# magnet_v2.net
KiCad netlist of a schematic drawn in EAGLE
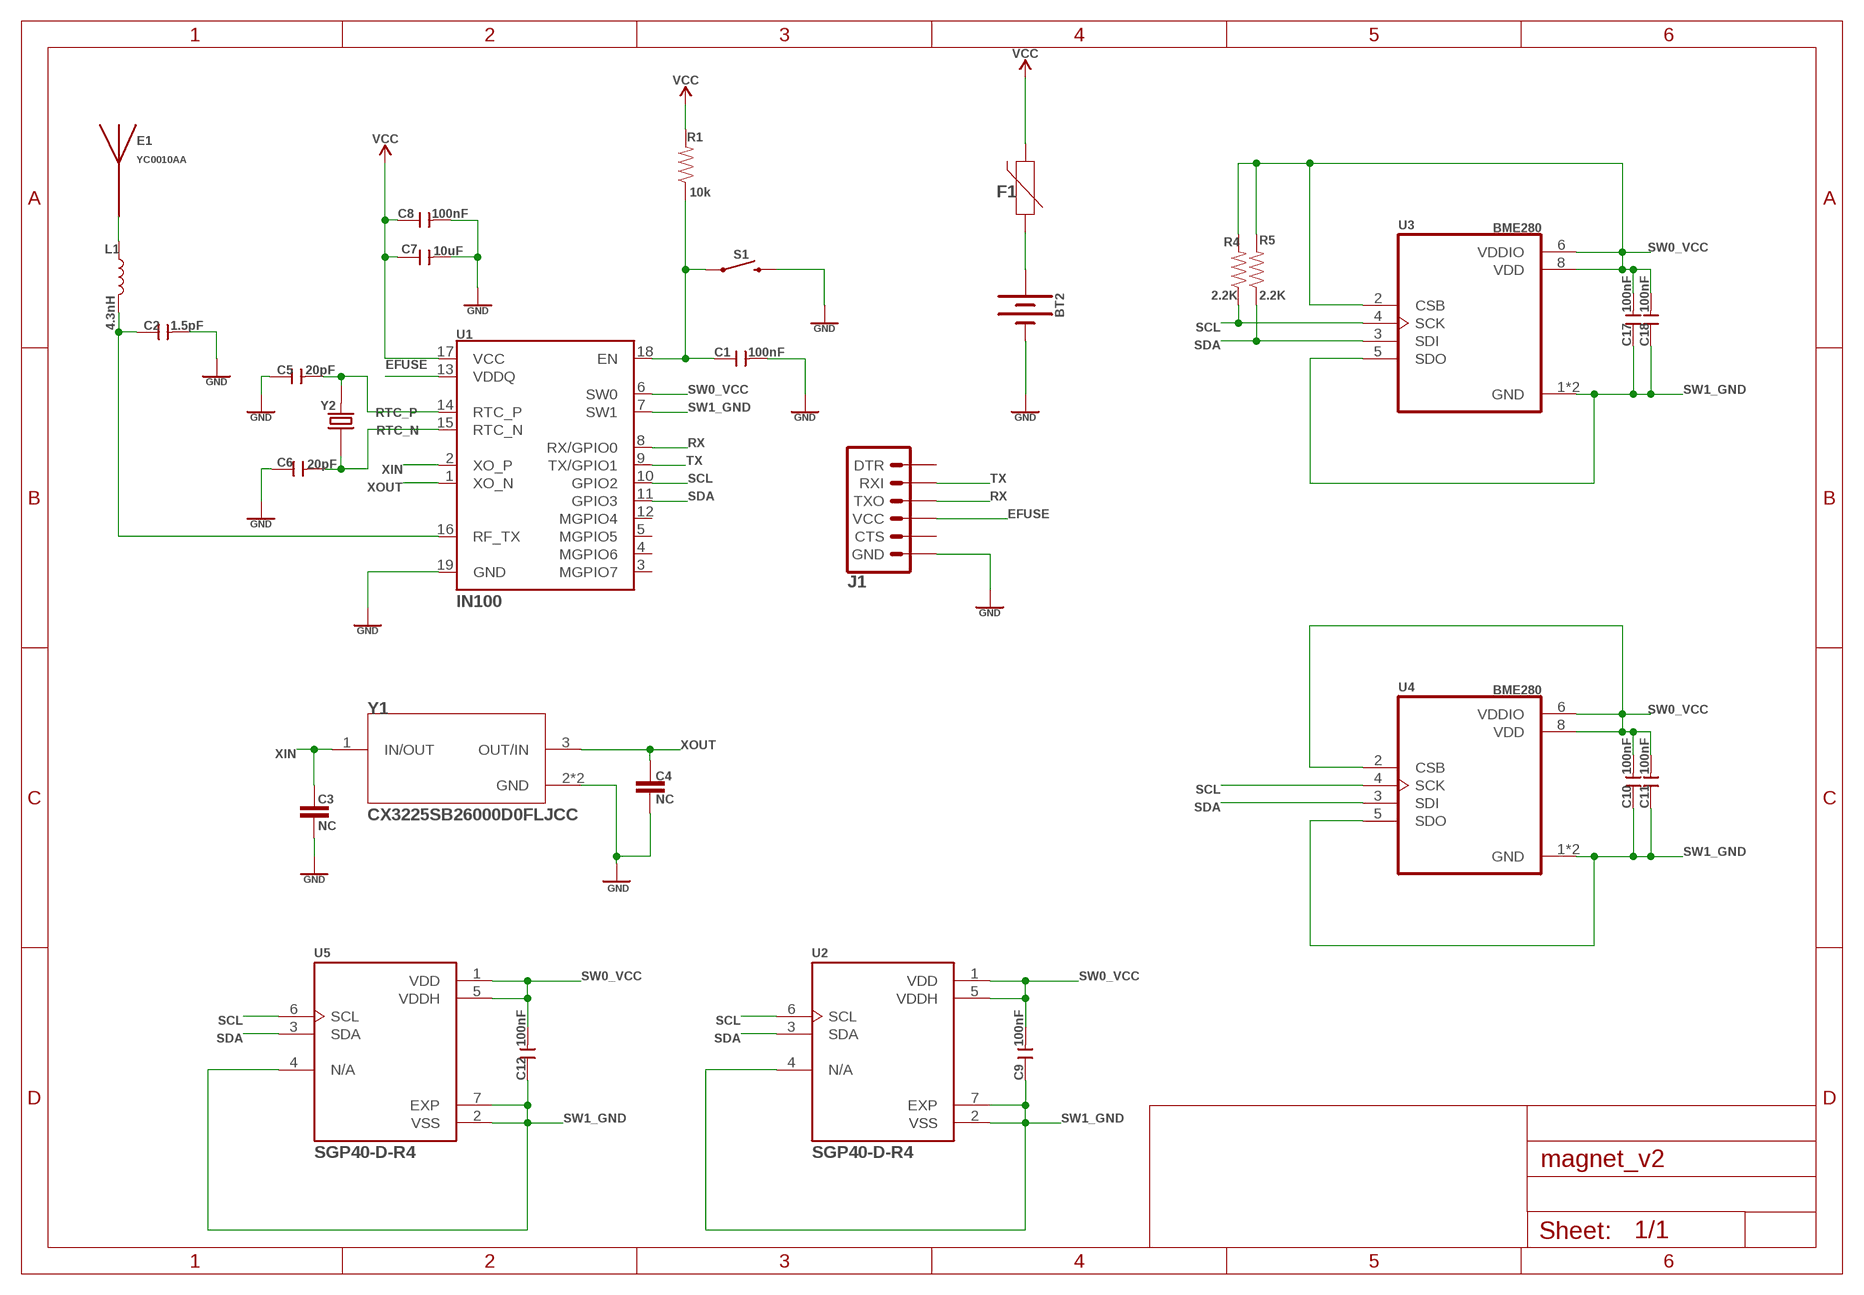
[diagram p0: schematic, sheet 1]

(export (version "E")
  (design (tool "Eeschema 10.0.6"))
  (components
    (comp (ref "BT2")
      (value "BATTERY-12MM_SMD")
      (footprint "eagle-import:BATTCON_12MM")
      (libsource (lib "eagle-import") (part "BATTERY-12MM_SMD"))
    )
    (comp (ref "C1")
      (value "100nF")
      (footprint "eagle-import:C0603")
      (fields (field (name "MPN") "CC0603KRX7R9BB104"))
      (libsource (lib "eagle-import") (part "CERAMIC-100NF-50V-10%-X7R(0603)"))
    )
    (comp (ref "C2")
      (value "1.5pF")
      (footprint "eagle-import:C0603")
      (fields (field (name "MPN") "CC0603JRNPO9BN100"))
      (libsource (lib "eagle-import") (part "CERAMIC-10PF-50V-5%-NPO(0603)"))
    )
    (comp (ref "C3")
      (value "NC")
      (footprint "eagle-import:0603")
      (libsource (lib "eagle-import") (part "12PF-0603-50V-5%"))
    )
    (comp (ref "C4")
      (value "NC")
      (footprint "eagle-import:0603")
      (libsource (lib "eagle-import") (part "12PF-0603-50V-5%"))
    )
    (comp (ref "C5")
      (value "20pF")
      (footprint "eagle-import:C0603")
      (fields (field (name "MPN") "CC0603JRNPO9BN220"))
      (libsource (lib "eagle-import") (part "CERAMIC-22PF-50V-5%-NPO(0603)"))
    )
    (comp (ref "C6")
      (value "20pF")
      (footprint "eagle-import:C0603")
      (fields (field (name "MPN") "CC0603JRNPO9BN220"))
      (libsource (lib "eagle-import") (part "CERAMIC-22PF-50V-5%-NPO(0603)"))
    )
    (comp (ref "C7")
      (value "10uF")
      (footprint "eagle-import:C0603")
      (fields (field (name "MPN") "CC0603KRX5R6BB106"))
      (libsource (lib "eagle-import") (part "CERAMIC-10UF-10V-10%-X5R(0603)"))
    )
    (comp (ref "C8")
      (value "100nF")
      (footprint "eagle-import:C0603")
      (fields (field (name "MPN") "CC0603KRX7R9BB104"))
      (libsource (lib "eagle-import") (part "CERAMIC-100NF-50V-10%-X7R(0603)"))
    )
    (comp (ref "C9")
      (value "100nF")
      (footprint "eagle-import:C0603")
      (fields (field (name "MPN") "CC0603KRX7R9BB104"))
      (libsource (lib "eagle-import") (part "CERAMIC-100NF-50V-10%-X7R(0603)"))
    )
    (comp (ref "C10")
      (value "100nF")
      (footprint "eagle-import:C0603")
      (fields (field (name "MPN") "CC0603KRX7R9BB104"))
      (libsource (lib "eagle-import") (part "CERAMIC-100NF-50V-10%-X7R(0603)"))
    )
    (comp (ref "C11")
      (value "100nF")
      (footprint "eagle-import:C0603")
      (fields (field (name "MPN") "CC0603KRX7R9BB104"))
      (libsource (lib "eagle-import") (part "CERAMIC-100NF-50V-10%-X7R(0603)"))
    )
    (comp (ref "C12")
      (value "100nF")
      (footprint "eagle-import:C0603")
      (fields (field (name "MPN") "CC0603KRX7R9BB104"))
      (libsource (lib "eagle-import") (part "CERAMIC-100NF-50V-10%-X7R(0603)"))
    )
    (comp (ref "C17")
      (value "100nF")
      (footprint "eagle-import:C0603")
      (fields (field (name "MPN") "CC0603KRX7R9BB104"))
      (libsource (lib "eagle-import") (part "CERAMIC-100NF-50V-10%-X7R(0603)"))
    )
    (comp (ref "C18")
      (value "100nF")
      (footprint "eagle-import:C0603")
      (fields (field (name "MPN") "CC0603KRX7R9BB104"))
      (libsource (lib "eagle-import") (part "CERAMIC-100NF-50V-10%-X7R(0603)"))
    )
    (comp (ref "E1")
      (value "YC0010AA")
      (footprint "eagle-import:XCVR_YC0010AA")
      (fields (field (name "MF") "Quectel"))
      (libsource (lib "eagle-import") (part "YC0010AA"))
    )
    (comp (ref "F1")
      (value "RESC3115X65N")
      (footprint "eagle-import:RESC3115X65N")
      (libsource (lib "eagle-import") (part "RESC3115X65N"))
    )
    (comp (ref "J1")
      (value "6_PIN_SERIAL_TARGETSMD")
      (footprint "eagle-import:1X06-SMD_RA_MALE")
      (libsource (lib "eagle-import") (part "6_PIN_SERIAL_TARGETSMD"))
    )
    (comp (ref "L1")
      (value "4.3nH")
      (footprint "eagle-import:0603")
      (libsource (lib "eagle-import") (part "INDUCTOR-0603-33NH"))
    )
    (comp (ref "R1")
      (value "10k")
      (footprint "eagle-import:0603")
      (libsource (lib "eagle-import") (part "10KOHM-0603-1/10W-1%"))
    )
    (comp (ref "R4")
      (value "2.2K")
      (footprint "eagle-import:0603")
      (libsource (lib "eagle-import") (part "2.2KOHM-0603-1/10W-1%"))
    )
    (comp (ref "R5")
      (value "2.2K")
      (footprint "eagle-import:0603")
      (libsource (lib "eagle-import") (part "2.2KOHM-0603-1/10W-1%"))
    )
    (comp (ref "S1")
      (value "MOMENTARY-SWITCH-SPST-SMD-4.6X2.8MM")
      (footprint "eagle-import:TACTILE_SWITCH_SMD_4.6X2.8MM")
      (libsource (lib "eagle-import") (part "MOMENTARY-SWITCH-SPST-SMD-4.6X2.8MM"))
    )
    (comp (ref "U1")
      (value "IN100")
      (footprint "eagle-import:IN100")
      (libsource (lib "eagle-import") (part "IN100"))
    )
    (comp (ref "U2")
      (value "SGP40-D-R4")
      (footprint "eagle-import:XCDR_SGP40-D-R4")
      (fields (field (name "MF") "Sensirion AG"))
      (libsource (lib "eagle-import") (part "SGP40-D-R4"))
    )
    (comp (ref "U3")
      (value "BME280")
      (footprint "eagle-import:PSON65P250X250X100-8N")
      (fields (field (name "MF") "Bosch"))
      (libsource (lib "eagle-import") (part "BME280"))
    )
    (comp (ref "U4")
      (value "BME280")
      (footprint "eagle-import:PSON65P250X250X100-8N")
      (fields (field (name "MF") "Bosch"))
      (libsource (lib "eagle-import") (part "BME280"))
    )
    (comp (ref "U5")
      (value "SGP40-D-R4")
      (footprint "eagle-import:XCDR_SGP40-D-R4")
      (fields (field (name "MF") "Sensirion AG"))
      (libsource (lib "eagle-import") (part "SGP40-D-R4"))
    )
    (comp (ref "Y1")
      (value "CX3225SB26000D0FLJCC")
      (footprint "eagle-import:XTAL_ECS-480-8-33B-CWY-TR3")
      (fields
        (field (name "MF") "ECS Inc.")
        (field (name "MP") "ECS-480-8-33B-CWY-TR3")
        (field (name "MF_1") "Kyocera")
        (field (name "MP_1") "CX3225SB26000D0FLJCC")
      )
      (libsource (lib "eagle-import") (part "ECS-480-8-33B-CWY-TR3"))
    )
    (comp (ref "Y2")
      (value "ECS-.327-12.5-16-TR")
      (footprint "eagle-import:XTAL_ECS-.327-12.5-16-TR")
      (fields (field (name "MF") "ECS Inc."))
      (libsource (lib "eagle-import") (part "ECS-.327-12.5-16-TR"))
    )
  )
  (nets
    (net (code "1") (name "EFUSE") (class "Default")
      (node (ref "J1") (pin "4") (pinfunction "VCC_4") (pintype "passive"))
      (node (ref "U1") (pin "13") (pinfunction "VDDQ_13") (pintype "power_in"))
    )
    (net (code "2") (name "GND") (class "Default")
      (node (ref "BT2") (pin "GND") (pinfunction "-_GND") (pintype "power_in"))
      (node (ref "C1") (pin "2") (pinfunction "2_2") (pintype "passive"))
      (node (ref "C2") (pin "2") (pinfunction "2_2") (pintype "passive"))
      (node (ref "C3") (pin "2") (pinfunction "2_2") (pintype "passive"))
      (node (ref "C4") (pin "2") (pinfunction "2_2") (pintype "passive"))
      (node (ref "C5") (pin "1") (pinfunction "1_1") (pintype "passive"))
      (node (ref "C6") (pin "1") (pinfunction "1_1") (pintype "passive"))
      (node (ref "C7") (pin "2") (pinfunction "2_2") (pintype "passive"))
      (node (ref "C8") (pin "2") (pinfunction "2_2") (pintype "passive"))
      (node (ref "J1") (pin "6") (pinfunction "GND_6") (pintype "passive"))
      (node (ref "S1") (pin "3") (pinfunction "2_3") (pintype "passive"))
      (node (ref "S1") (pin "4") (pinfunction "2_4") (pintype "passive"))
      (node (ref "U1") (pin "19") (pinfunction "GND_19") (pintype "power_in"))
      (node (ref "Y1") (pin "2") (pinfunction "GND_2") (pintype "power_in"))
      (node (ref "Y1") (pin "4") (pinfunction "GND_4") (pintype "power_in"))
    )
    (net (code "3") (name "Net-(BT2-+)") (class "Default")
      (node (ref "BT2") (pin "PWR@1") (pinfunction "+_PWR@1") (pintype "power_in"))
      (node (ref "F1") (pin "1") (pinfunction "1_1") (pintype "bidirectional"))
    )
    (net (code "4") (name "Net-(E1-Pad1)") (class "Default")
      (node (ref "E1") (pin "1") (pinfunction "1_1") (pintype "input"))
      (node (ref "L1") (pin "1") (pinfunction "1_1") (pintype "passive"))
    )
    (net (code "5") (name "Net-(U1-EN)") (class "Default")
      (node (ref "C1") (pin "1") (pinfunction "1_1") (pintype "passive"))
      (node (ref "R1") (pin "1") (pinfunction "1_1") (pintype "passive"))
      (node (ref "S1") (pin "1") (pinfunction "1_1") (pintype "passive"))
      (node (ref "S1") (pin "2") (pinfunction "1_2") (pintype "passive"))
      (node (ref "U1") (pin "18") (pinfunction "EN_18") (pintype "input"))
    )
    (net (code "6") (name "Net-(U1-RF_TX)") (class "Default")
      (node (ref "C2") (pin "1") (pinfunction "1_1") (pintype "passive"))
      (node (ref "L1") (pin "2") (pinfunction "2_2") (pintype "passive"))
      (node (ref "U1") (pin "16") (pinfunction "RF_TX_16") (pintype "bidirectional"))
    )
    (net (code "7") (name "RTC_N") (class "Default")
      (node (ref "C6") (pin "2") (pinfunction "2_2") (pintype "passive"))
      (node (ref "U1") (pin "15") (pinfunction "RTC_N_15") (pintype "bidirectional"))
      (node (ref "Y2") (pin "1") (pinfunction "1_1") (pintype "passive"))
    )
    (net (code "8") (name "RTC_P") (class "Default")
      (node (ref "C5") (pin "2") (pinfunction "2_2") (pintype "passive"))
      (node (ref "U1") (pin "14") (pinfunction "RTC_P_14") (pintype "bidirectional"))
      (node (ref "Y2") (pin "2") (pinfunction "2_2") (pintype "passive"))
    )
    (net (code "9") (name "RX") (class "Default")
      (node (ref "J1") (pin "3") (pinfunction "TXO_3") (pintype "passive"))
      (node (ref "U1") (pin "8") (pinfunction "RX/GPIO0_8") (pintype "bidirectional"))
    )
    (net (code "10") (name "SCL") (class "Default")
      (node (ref "R4") (pin "1") (pinfunction "1_1") (pintype "passive"))
      (node (ref "U1") (pin "10") (pinfunction "GPIO2_10") (pintype "bidirectional"))
      (node (ref "U2") (pin "6") (pinfunction "SCL_6") (pintype "bidirectional"))
      (node (ref "U3") (pin "4") (pinfunction "SCK_4") (pintype "input"))
      (node (ref "U4") (pin "4") (pinfunction "SCK_4") (pintype "input"))
      (node (ref "U5") (pin "6") (pinfunction "SCL_6") (pintype "bidirectional"))
    )
    (net (code "11") (name "SDA") (class "Default")
      (node (ref "R5") (pin "1") (pinfunction "1_1") (pintype "passive"))
      (node (ref "U1") (pin "11") (pinfunction "GPIO3_11") (pintype "bidirectional"))
      (node (ref "U2") (pin "3") (pinfunction "SDA_3") (pintype "bidirectional"))
      (node (ref "U3") (pin "3") (pinfunction "SDI_3") (pintype "bidirectional"))
      (node (ref "U4") (pin "3") (pinfunction "SDI_3") (pintype "bidirectional"))
      (node (ref "U5") (pin "3") (pinfunction "SDA_3") (pintype "bidirectional"))
    )
    (net (code "12") (name "SW0_VCC") (class "Default")
      (node (ref "C10") (pin "2") (pinfunction "2_2") (pintype "passive"))
      (node (ref "C11") (pin "2") (pinfunction "2_2") (pintype "passive"))
      (node (ref "C12") (pin "2") (pinfunction "2_2") (pintype "passive"))
      (node (ref "C17") (pin "2") (pinfunction "2_2") (pintype "passive"))
      (node (ref "C18") (pin "2") (pinfunction "2_2") (pintype "passive"))
      (node (ref "C9") (pin "2") (pinfunction "2_2") (pintype "passive"))
      (node (ref "R4") (pin "2") (pinfunction "2_2") (pintype "passive"))
      (node (ref "R5") (pin "2") (pinfunction "2_2") (pintype "passive"))
      (node (ref "U1") (pin "6") (pinfunction "SW0_6") (pintype "output"))
      (node (ref "U2") (pin "1") (pinfunction "VDD_1") (pintype "power_in"))
      (node (ref "U2") (pin "5") (pinfunction "VDDH_5") (pintype "power_in"))
      (node (ref "U3") (pin "2") (pinfunction "CSB_2") (pintype "input"))
      (node (ref "U3") (pin "6") (pinfunction "VDDIO_6") (pintype "power_in"))
      (node (ref "U3") (pin "8") (pinfunction "VDD_8") (pintype "power_in"))
      (node (ref "U4") (pin "2") (pinfunction "CSB_2") (pintype "input"))
      (node (ref "U4") (pin "6") (pinfunction "VDDIO_6") (pintype "power_in"))
      (node (ref "U4") (pin "8") (pinfunction "VDD_8") (pintype "power_in"))
      (node (ref "U5") (pin "1") (pinfunction "VDD_1") (pintype "power_in"))
      (node (ref "U5") (pin "5") (pinfunction "VDDH_5") (pintype "power_in"))
    )
    (net (code "13") (name "SW1_GND") (class "Default")
      (node (ref "C10") (pin "1") (pinfunction "1_1") (pintype "passive"))
      (node (ref "C11") (pin "1") (pinfunction "1_1") (pintype "passive"))
      (node (ref "C12") (pin "1") (pinfunction "1_1") (pintype "passive"))
      (node (ref "C17") (pin "1") (pinfunction "1_1") (pintype "passive"))
      (node (ref "C18") (pin "1") (pinfunction "1_1") (pintype "passive"))
      (node (ref "C9") (pin "1") (pinfunction "1_1") (pintype "passive"))
      (node (ref "U1") (pin "7") (pinfunction "SW1_7") (pintype "output"))
      (node (ref "U2") (pin "2") (pinfunction "VSS_2") (pintype "power_in"))
      (node (ref "U2") (pin "4") (pinfunction "N/A_4") (pintype "passive"))
      (node (ref "U2") (pin "7") (pinfunction "EXP_7") (pintype "power_in"))
      (node (ref "U3") (pin "1") (pinfunction "GND_1") (pintype "power_in"))
      (node (ref "U3") (pin "5") (pinfunction "SDO_5") (pintype "bidirectional"))
      (node (ref "U3") (pin "7") (pinfunction "GND_7") (pintype "power_in"))
      (node (ref "U4") (pin "1") (pinfunction "GND_1") (pintype "power_in"))
      (node (ref "U4") (pin "5") (pinfunction "SDO_5") (pintype "bidirectional"))
      (node (ref "U4") (pin "7") (pinfunction "GND_7") (pintype "power_in"))
      (node (ref "U5") (pin "2") (pinfunction "VSS_2") (pintype "power_in"))
      (node (ref "U5") (pin "4") (pinfunction "N/A_4") (pintype "passive"))
      (node (ref "U5") (pin "7") (pinfunction "EXP_7") (pintype "power_in"))
    )
    (net (code "14") (name "TX") (class "Default")
      (node (ref "J1") (pin "2") (pinfunction "RXI_2") (pintype "passive"))
      (node (ref "U1") (pin "9") (pinfunction "TX/GPIO1_9") (pintype "bidirectional"))
    )
    (net (code "15") (name "VCC") (class "Default")
      (node (ref "C7") (pin "1") (pinfunction "1_1") (pintype "passive"))
      (node (ref "C8") (pin "1") (pinfunction "1_1") (pintype "passive"))
      (node (ref "F1") (pin "2") (pinfunction "2_2") (pintype "bidirectional"))
      (node (ref "R1") (pin "2") (pinfunction "2_2") (pintype "passive"))
      (node (ref "U1") (pin "17") (pinfunction "VCC_17") (pintype "power_in"))
    )
    (net (code "16") (name "XIN") (class "Default")
      (node (ref "C3") (pin "1") (pinfunction "1_1") (pintype "passive"))
      (node (ref "U1") (pin "2") (pinfunction "XO_P_2") (pintype "bidirectional"))
      (node (ref "Y1") (pin "1") (pinfunction "IN/OUT_1") (pintype "bidirectional"))
    )
    (net (code "17") (name "XOUT") (class "Default")
      (node (ref "C4") (pin "1") (pinfunction "1_1") (pintype "passive"))
      (node (ref "U1") (pin "1") (pinfunction "XO_N_1") (pintype "bidirectional"))
      (node (ref "Y1") (pin "3") (pinfunction "OUT/IN_3") (pintype "bidirectional"))
    )
    (net (code "18") (name "unconnected-(J1-CTS-Pad5)") (class "Default")
      (node (ref "J1") (pin "5") (pinfunction "CTS_5") (pintype "passive"))
    )
    (net (code "19") (name "unconnected-(J1-DTR-Pad1)") (class "Default")
      (node (ref "J1") (pin "1") (pinfunction "DTR_1") (pintype "passive"))
    )
    (net (code "20") (name "unconnected-(U1-MGPIO4-Pad12)") (class "Default")
      (node (ref "U1") (pin "12") (pinfunction "MGPIO4_12") (pintype "bidirectional"))
    )
    (net (code "21") (name "unconnected-(U1-MGPIO5-Pad5)") (class "Default")
      (node (ref "U1") (pin "5") (pinfunction "MGPIO5_5") (pintype "bidirectional"))
    )
    (net (code "22") (name "unconnected-(U1-MGPIO6-Pad4)") (class "Default")
      (node (ref "U1") (pin "4") (pinfunction "MGPIO6_4") (pintype "bidirectional"))
    )
    (net (code "23") (name "unconnected-(U1-MGPIO7-Pad3)") (class "Default")
      (node (ref "U1") (pin "3") (pinfunction "MGPIO7_3") (pintype "bidirectional"))
    )
  )
)
